# RF_Front_End.net
KiCad netlist of a schematic drawn in Altium Designer
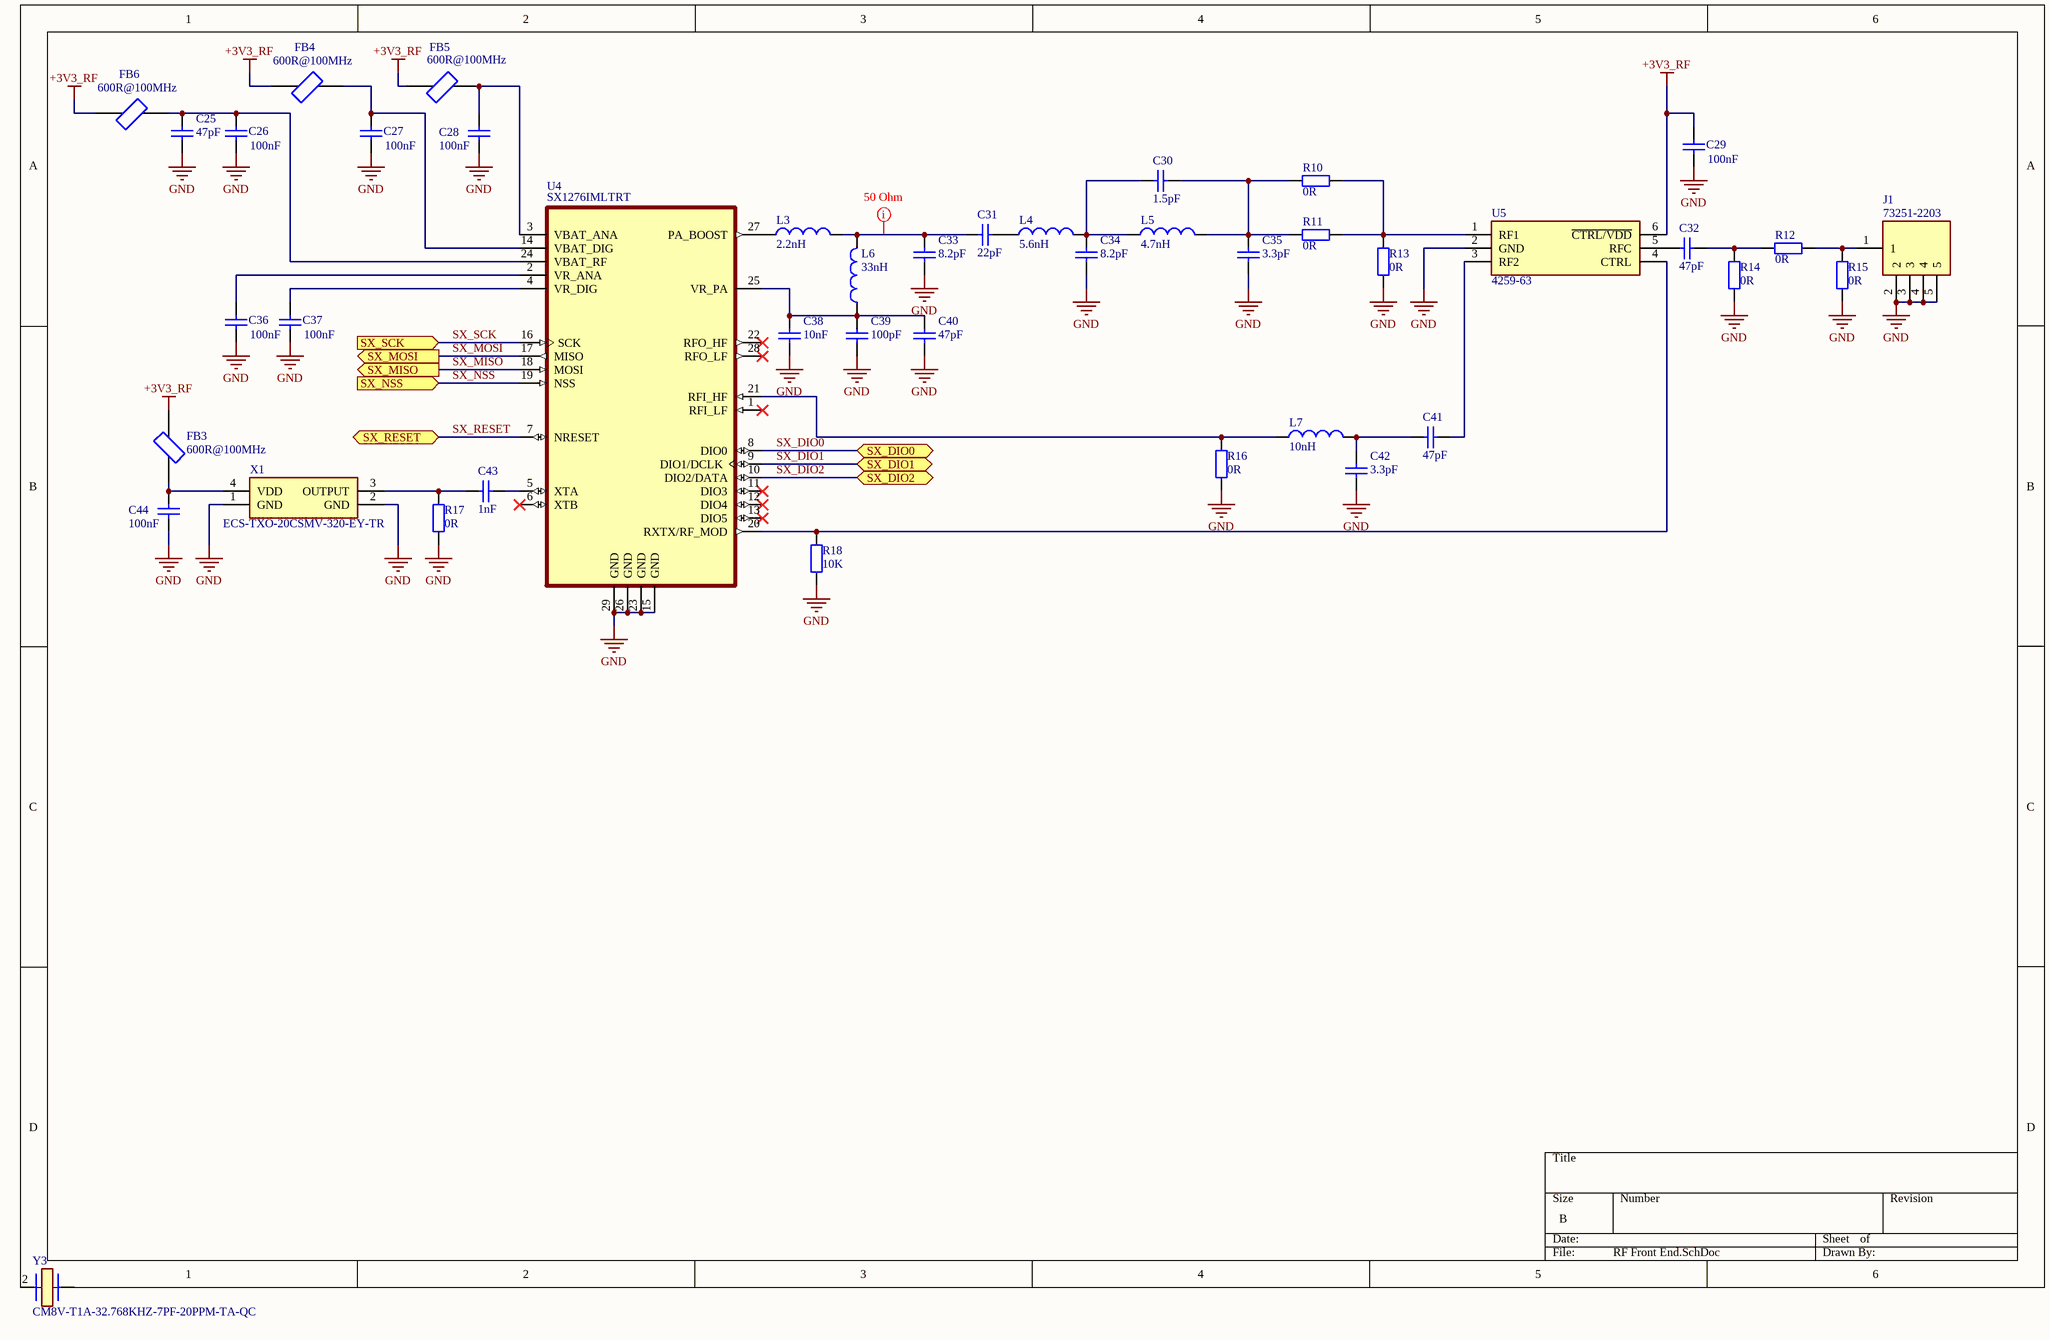
[diagram p0: RF Front End.SchDoc]

(export (version "E")
  (design (tool "Eeschema 10.0.6"))
  (components
    (comp (ref "C25")
      (value "47pF")
      (footprint "0402")
      (description "Capacitor")
      (fields (field (name "Comment") "Cap") (field (name "PUBLISHER") "Altium Limited"))
      (libsource (lib "Miscellaneous Devices") (part "Cap"))
    )
    (comp (ref "C26")
      (value "100nF")
      (footprint "0402")
      (description "Capacitor")
      (fields (field (name "PUBLISHER") "Altium Limited"))
      (libsource (lib "Miscellaneous Devices") (part "Cap"))
    )
    (comp (ref "C27")
      (value "100nF")
      (footprint "0402")
      (description "Capacitor")
      (fields (field (name "PUBLISHER") "Altium Limited"))
      (libsource (lib "Miscellaneous Devices") (part "Cap"))
    )
    (comp (ref "C28")
      (value "100nF")
      (footprint "0402")
      (description "Capacitor")
      (fields (field (name "PUBLISHER") "Altium Limited"))
      (libsource (lib "Miscellaneous Devices") (part "Cap"))
    )
    (comp (ref "C29")
      (value "100nF")
      (footprint "0402")
      (description "Capacitor")
      (fields (field (name "PUBLISHER") "Altium Limited"))
      (libsource (lib "Miscellaneous Devices") (part "Cap"))
    )
    (comp (ref "C30")
      (value "1.5pF")
      (footprint "0402")
      (description "Capacitor")
      (fields (field (name "Comment") "Cap") (field (name "PUBLISHER") "Altium Limited"))
      (libsource (lib "Miscellaneous Devices") (part "Cap"))
    )
    (comp (ref "C31")
      (value "22pF")
      (footprint "0402")
      (description "Capacitor")
      (fields (field (name "Comment") "Cap") (field (name "PUBLISHER") "Altium Limited"))
      (libsource (lib "Miscellaneous Devices") (part "Cap"))
    )
    (comp (ref "C32")
      (value "47pF")
      (footprint "0402")
      (description "Capacitor")
      (fields (field (name "Comment") "Cap") (field (name "PUBLISHER") "Altium Limited"))
      (libsource (lib "Miscellaneous Devices") (part "Cap"))
    )
    (comp (ref "C33")
      (value "8.2pF")
      (footprint "0402")
      (description "Capacitor")
      (fields (field (name "Comment") "Cap") (field (name "PUBLISHER") "Altium Limited"))
      (libsource (lib "Miscellaneous Devices") (part "Cap"))
    )
    (comp (ref "C34")
      (value "8.2pF")
      (footprint "0402")
      (description "Capacitor")
      (fields (field (name "Comment") "Cap") (field (name "PUBLISHER") "Altium Limited"))
      (libsource (lib "Miscellaneous Devices") (part "Cap"))
    )
    (comp (ref "C35")
      (value "3.3pF")
      (footprint "0402")
      (description "Capacitor")
      (fields (field (name "Comment") "Cap") (field (name "PUBLISHER") "Altium Limited"))
      (libsource (lib "Miscellaneous Devices") (part "Cap"))
    )
    (comp (ref "C36")
      (value "100nF")
      (footprint "0402")
      (description "Capacitor")
      (fields (field (name "PUBLISHER") "Altium Limited"))
      (libsource (lib "Miscellaneous Devices") (part "Cap"))
    )
    (comp (ref "C37")
      (value "100nF")
      (footprint "0402")
      (description "Capacitor")
      (fields (field (name "PUBLISHER") "Altium Limited"))
      (libsource (lib "Miscellaneous Devices") (part "Cap"))
    )
    (comp (ref "C38")
      (value "10nF")
      (footprint "0402")
      (description "Capacitor")
      (fields (field (name "Comment") "Cap") (field (name "PUBLISHER") "Altium Limited"))
      (libsource (lib "Miscellaneous Devices") (part "Cap"))
    )
    (comp (ref "C39")
      (value "100pF")
      (footprint "0402")
      (description "Capacitor")
      (fields (field (name "Comment") "Cap") (field (name "PUBLISHER") "Altium Limited"))
      (libsource (lib "Miscellaneous Devices") (part "Cap"))
    )
    (comp (ref "C40")
      (value "47pF")
      (footprint "0402")
      (description "Capacitor")
      (fields (field (name "Comment") "Cap") (field (name "PUBLISHER") "Altium Limited"))
      (libsource (lib "Miscellaneous Devices") (part "Cap"))
    )
    (comp (ref "C41")
      (value "47pF")
      (footprint "0402")
      (description "Capacitor")
      (fields (field (name "Comment") "Cap") (field (name "PUBLISHER") "Altium Limited"))
      (libsource (lib "Miscellaneous Devices") (part "Cap"))
    )
    (comp (ref "C42")
      (value "3.3pF")
      (footprint "0402")
      (description "Capacitor")
      (fields (field (name "Comment") "Cap") (field (name "PUBLISHER") "Altium Limited"))
      (libsource (lib "Miscellaneous Devices") (part "Cap"))
    )
    (comp (ref "C43")
      (value "1nF")
      (footprint "0402")
      (description "Capacitor")
      (fields (field (name "PUBLISHER") "Altium Limited"))
      (libsource (lib "Miscellaneous Devices") (part "Cap"))
    )
    (comp (ref "C44")
      (value "100nF")
      (footprint "0402")
      (description "Capacitor")
      (fields (field (name "PUBLISHER") "Altium Limited"))
      (libsource (lib "Miscellaneous Devices") (part "Cap"))
    )
    (comp (ref "FB3")
      (value "600R@100MHz")
      (footprint "0402 Ferrite Bead")
      (description "Ferrite Beads FERRITE BEAD 600 OHM 0603 1LN")
      (fields (field (name "MF") "Laird-Signal Integrity Products") (field (name "MP") "MI0805K400R-10"))
      (libsource (lib "Schematic_library") (part "Ferrite"))
    )
    (comp (ref "FB4")
      (value "600R@100MHz")
      (footprint "0402 Ferrite Bead")
      (description "Ferrite Beads FERRITE BEAD 600 OHM 0603 1LN")
      (fields (field (name "MF") "Laird-Signal Integrity Products") (field (name "MP") "MI0805K400R-10"))
      (libsource (lib "Schematic_library") (part "Ferrite"))
    )
    (comp (ref "FB5")
      (value "600R@100MHz")
      (footprint "0402 Ferrite Bead")
      (description "Ferrite Beads FERRITE BEAD 600 OHM 0603 1LN")
      (fields (field (name "MF") "Laird-Signal Integrity Products") (field (name "MP") "MI0805K400R-10"))
      (libsource (lib "Schematic_library") (part "Ferrite"))
    )
    (comp (ref "FB6")
      (value "600R@100MHz")
      (footprint "0402 Ferrite Bead")
      (description "Ferrite Beads FERRITE BEAD 600 OHM 0603 1LN")
      (fields (field (name "MF") "Laird-Signal Integrity Products") (field (name "MP") "MI0805K400R-10"))
      (libsource (lib "Schematic_library") (part "Ferrite"))
    )
    (comp (ref "J1")
      (value "73251-2203")
      (footprint "732512203")
      (description "RF Connectors / Coaxial Connectors Conn 50 Ohms, SMA Jack, Right-Angle PCB, Gold")
      (fields (field (name "MOUSER PART NUMBER") "538-73251-2203"))
      (libsource (lib "Schematic_library") (part "73251-2203"))
    )
    (comp (ref "L3")
      (value "2.2nH")
      (footprint "0402-A")
      (description "Inductor")
      (fields (field (name "PUBLISHER") "Altium Limited"))
      (libsource (lib "Miscellaneous Devices") (part "Inductor"))
    )
    (comp (ref "L4")
      (value "5.6nH")
      (footprint "0402-A")
      (description "Inductor")
      (fields (field (name "PUBLISHER") "Altium Limited"))
      (libsource (lib "Miscellaneous Devices") (part "Inductor"))
    )
    (comp (ref "L5")
      (value "4.7nH")
      (footprint "0402-A")
      (description "Inductor")
      (fields (field (name "PUBLISHER") "Altium Limited"))
      (libsource (lib "Miscellaneous Devices") (part "Inductor"))
    )
    (comp (ref "L6")
      (value "33nH")
      (footprint "0402-A")
      (description "Inductor")
      (fields (field (name "PUBLISHER") "Altium Limited"))
      (libsource (lib "Miscellaneous Devices") (part "Inductor"))
    )
    (comp (ref "L7")
      (value "10nH")
      (footprint "0402-A")
      (description "Inductor")
      (fields (field (name "PUBLISHER") "Altium Limited"))
      (libsource (lib "Miscellaneous Devices") (part "Inductor"))
    )
    (comp (ref "R10")
      (value "0R")
      (footprint "SMD-0402-RES")
      (description "Resistor")
      (fields (field (name "PUBLISHER") "Altium Limited"))
      (libsource (lib "") (part "Res2_2"))
    )
    (comp (ref "R11")
      (value "0R")
      (footprint "SMD-0402-RES")
      (description "Resistor")
      (fields (field (name "PUBLISHER") "Altium Limited"))
      (libsource (lib "") (part "Res2_2"))
    )
    (comp (ref "R12")
      (value "0R")
      (footprint "SMD-0402-RES")
      (description "Resistor")
      (fields (field (name "PUBLISHER") "Altium Limited"))
      (libsource (lib "") (part "Res2_1"))
    )
    (comp (ref "R13")
      (value "0R")
      (footprint "SMD-0402-RES")
      (description "Resistor")
      (fields (field (name "PUBLISHER") "Altium Limited"))
      (libsource (lib "Miscellaneous Devices") (part "Res2"))
    )
    (comp (ref "R14")
      (value "0R")
      (footprint "SMD-0402-RES")
      (description "Resistor")
      (fields (field (name "PUBLISHER") "Altium Limited"))
      (libsource (lib "Miscellaneous Devices") (part "Res2"))
    )
    (comp (ref "R15")
      (value "0R")
      (footprint "SMD-0402-RES")
      (description "Resistor")
      (fields (field (name "PUBLISHER") "Altium Limited"))
      (libsource (lib "Miscellaneous Devices") (part "Res2"))
    )
    (comp (ref "R16")
      (value "0R")
      (footprint "SMD-0402-RES")
      (description "Resistor")
      (fields (field (name "PUBLISHER") "Altium Limited"))
      (libsource (lib "Miscellaneous Devices") (part "Res2"))
    )
    (comp (ref "R17")
      (value "0R")
      (footprint "SMD-0402-RES")
      (description "Resistor")
      (fields (field (name "PUBLISHER") "Altium Limited"))
      (libsource (lib "Miscellaneous Devices") (part "Res2"))
    )
    (comp (ref "R18")
      (value "10K")
      (footprint "SMD-0402-RES")
      (description "Resistor")
      (fields (field (name "PUBLISHER") "Altium Limited"))
      (libsource (lib "Miscellaneous Devices") (part "Res2"))
    )
    (comp (ref "U4")
      (value "SX1276IMLTRT")
      (footprint "SX1276IMLTRT")
      (description "IC RF TxRx Only 802.15.4 LoRaâ„¢ 137MHz ~ 1.02GHz 28-VQFN Exposed Pad")
      (fields (field (name "MF") "Semtech Corporation"))
      (libsource (lib "Schematic_library") (part "SX1276IMLTRT"))
    )
    (comp (ref "U5")
      (value "4259-63")
      (footprint "4259-63")
      (description "RF switch IC")
      (fields (field (name "MOUSER PART NUMBER") "81-4259-63"))
      (libsource (lib "Schematic_library") (part "4259-63"))
    )
    (comp (ref "X1")
      (value "ECS-TXO-20CSMV-320-EY-TR")
      (footprint "ECS-TXO-20CSMV-320-EY-TR")
      (description "TCXO Oscillators MultiVolt TCXO,32MHz,+/-2.5ppm,1.7V 3.465V,2.5 mA,-30 C 85 C, 2.00mm x 1.60mm")
      (fields (field (name "MOUSER PART NUMBER") "520-TXO20CSMV320EYTR"))
      (libsource (lib "Schematic_library") (part "ECS-TXO-20CSMV-320-EY-TR"))
    )
    (comp (ref "Y3")
      (value "CM8V-T1A-32.768KHZ-7PF-20PPM-TA-QC")
      (footprint "SamacSys:CM8V32768TA020125")
      (description "Crystal or Oscillator")
      (fields (field (name "MOUSER PART NUMBER") "428-201436-MC01"))
      (libsource (lib "*") (part "CM8V-T1A-32.768KHZ-7PF-20PPM-TA-QC"))
    )
  )
  (nets
    (net (code "1") (name "+3V3_RF") (class "Default")
      (node (ref "C29") (pin "2") (pinfunction "2_2") (pintype "passive"))
      (node (ref "FB3") (pin "2") (pinfunction "2_2") (pintype "passive"))
      (node (ref "FB4") (pin "1") (pinfunction "1_1") (pintype "passive"))
      (node (ref "FB5") (pin "1") (pinfunction "1_1") (pintype "passive"))
      (node (ref "FB6") (pin "1") (pinfunction "1_1") (pintype "passive"))
      (node (ref "U5") (pin "6") (pinfunction "~{CTRL/VDD}_6") (pintype "passive"))
    )
    (net (code "2") (name "/SX_DIO0") (class "Default")
      (node (ref "U4") (pin "8") (pinfunction "DIO0_8") (pintype "bidirectional"))
    )
    (net (code "3") (name "/SX_DIO1") (class "Default")
      (node (ref "U4") (pin "9") (pinfunction "DIO1/DCLK_9") (pintype "bidirectional"))
    )
    (net (code "4") (name "/SX_DIO2") (class "Default")
      (node (ref "U4") (pin "10") (pinfunction "DIO2/DATA_10") (pintype "bidirectional"))
    )
    (net (code "5") (name "/SX_MISO") (class "Default")
      (node (ref "U4") (pin "18") (pinfunction "MOSI_18") (pintype "input"))
    )
    (net (code "6") (name "/SX_MOSI") (class "Default")
      (node (ref "U4") (pin "17") (pinfunction "MISO_17") (pintype "output"))
    )
    (net (code "7") (name "/SX_NSS") (class "Default")
      (node (ref "U4") (pin "19") (pinfunction "NSS_19") (pintype "input"))
    )
    (net (code "8") (name "/SX_RESET") (class "Default")
      (node (ref "U4") (pin "7") (pinfunction "NRESET_7") (pintype "bidirectional"))
    )
    (net (code "9") (name "/SX_SCK") (class "Default")
      (node (ref "U4") (pin "16") (pinfunction "SCK_16") (pintype "input"))
    )
    (net (code "10") (name "GND") (class "Default")
      (node (ref "C25") (pin "1") (pinfunction "1_1") (pintype "passive"))
      (node (ref "C26") (pin "1") (pinfunction "1_1") (pintype "passive"))
      (node (ref "C27") (pin "1") (pinfunction "1_1") (pintype "passive"))
      (node (ref "C28") (pin "1") (pinfunction "1_1") (pintype "passive"))
      (node (ref "C29") (pin "1") (pinfunction "1_1") (pintype "passive"))
      (node (ref "C33") (pin "1") (pinfunction "1_1") (pintype "passive"))
      (node (ref "C34") (pin "1") (pinfunction "1_1") (pintype "passive"))
      (node (ref "C35") (pin "1") (pinfunction "1_1") (pintype "passive"))
      (node (ref "C36") (pin "1") (pinfunction "1_1") (pintype "passive"))
      (node (ref "C37") (pin "1") (pinfunction "1_1") (pintype "passive"))
      (node (ref "C38") (pin "1") (pinfunction "1_1") (pintype "passive"))
      (node (ref "C39") (pin "1") (pinfunction "1_1") (pintype "passive"))
      (node (ref "C40") (pin "1") (pinfunction "1_1") (pintype "passive"))
      (node (ref "C42") (pin "1") (pinfunction "1_1") (pintype "passive"))
      (node (ref "C44") (pin "1") (pinfunction "1_1") (pintype "passive"))
      (node (ref "J1") (pin "2") (pinfunction "2_2") (pintype "passive"))
      (node (ref "J1") (pin "3") (pinfunction "3_3") (pintype "passive"))
      (node (ref "J1") (pin "4") (pinfunction "4_4") (pintype "passive"))
      (node (ref "J1") (pin "5") (pinfunction "5_5") (pintype "passive"))
      (node (ref "R13") (pin "1") (pinfunction "1_1") (pintype "passive"))
      (node (ref "R14") (pin "1") (pinfunction "1_1") (pintype "passive"))
      (node (ref "R15") (pin "1") (pinfunction "1_1") (pintype "passive"))
      (node (ref "R16") (pin "1") (pinfunction "1_1") (pintype "passive"))
      (node (ref "R17") (pin "1") (pinfunction "1_1") (pintype "passive"))
      (node (ref "R18") (pin "1") (pinfunction "1_1") (pintype "passive"))
      (node (ref "U4") (pin "15") (pinfunction "GND_15") (pintype "power_in"))
      (node (ref "U4") (pin "23") (pinfunction "GND_23") (pintype "power_in"))
      (node (ref "U4") (pin "26") (pinfunction "GND_26") (pintype "power_in"))
      (node (ref "U4") (pin "29") (pinfunction "GND_29") (pintype "power_in"))
      (node (ref "U5") (pin "2") (pinfunction "GND_2") (pintype "passive"))
      (node (ref "X1") (pin "1") (pinfunction "GND_1") (pintype "passive"))
      (node (ref "X1") (pin "2") (pinfunction "GND_2") (pintype "passive"))
    )
    (net (code "11") (name "Net-(C30-Pad1)") (class "Default")
      (node (ref "C30") (pin "1") (pinfunction "1_1") (pintype "passive"))
      (node (ref "C35") (pin "2") (pinfunction "2_2") (pintype "passive"))
      (node (ref "L5") (pin "2") (pinfunction "2_2") (pintype "passive"))
      (node (ref "R10") (pin "1") (pinfunction "1_1") (pintype "passive"))
      (node (ref "R11") (pin "1") (pinfunction "1_1") (pintype "passive"))
    )
    (net (code "12") (name "Net-(C30-Pad2)") (class "Default")
      (node (ref "C30") (pin "2") (pinfunction "2_2") (pintype "passive"))
      (node (ref "C34") (pin "2") (pinfunction "2_2") (pintype "passive"))
      (node (ref "L4") (pin "2") (pinfunction "2_2") (pintype "passive"))
      (node (ref "L5") (pin "1") (pinfunction "1_1") (pintype "passive"))
    )
    (net (code "13") (name "Net-(C31-Pad1)") (class "Default")
      (node (ref "C31") (pin "1") (pinfunction "1_1") (pintype "passive"))
      (node (ref "L4") (pin "1") (pinfunction "1_1") (pintype "passive"))
    )
    (net (code "14") (name "Net-(C31-Pad2)") (class "Default")
      (node (ref "C31") (pin "2") (pinfunction "2_2") (pintype "passive"))
      (node (ref "C33") (pin "2") (pinfunction "2_2") (pintype "passive"))
      (node (ref "L3") (pin "2") (pinfunction "2_2") (pintype "passive"))
      (node (ref "L6") (pin "2") (pinfunction "2_2") (pintype "passive"))
    )
    (net (code "15") (name "Net-(C32-Pad1)") (class "Default")
      (node (ref "C32") (pin "1") (pinfunction "1_1") (pintype "passive"))
      (node (ref "R12") (pin "2") (pinfunction "2_2") (pintype "passive"))
      (node (ref "R14") (pin "2") (pinfunction "2_2") (pintype "passive"))
    )
    (net (code "16") (name "Net-(C41-Pad2)") (class "Default")
      (node (ref "C41") (pin "2") (pinfunction "2_2") (pintype "passive"))
      (node (ref "C42") (pin "2") (pinfunction "2_2") (pintype "passive"))
      (node (ref "L7") (pin "2") (pinfunction "2_2") (pintype "passive"))
    )
    (net (code "17") (name "Net-(J1-Pad1)") (class "Default")
      (node (ref "J1") (pin "1") (pinfunction "1_1") (pintype "passive"))
      (node (ref "R12") (pin "1") (pinfunction "1_1") (pintype "passive"))
      (node (ref "R15") (pin "2") (pinfunction "2_2") (pintype "passive"))
    )
    (net (code "18") (name "Net-(U4-PA_BOOST)") (class "Default")
      (node (ref "L3") (pin "1") (pinfunction "1_1") (pintype "passive"))
      (node (ref "U4") (pin "27") (pinfunction "PA_BOOST_27") (pintype "output"))
    )
    (net (code "19") (name "Net-(U4-RFI_HF)") (class "Default")
      (node (ref "L7") (pin "1") (pinfunction "1_1") (pintype "passive"))
      (node (ref "R16") (pin "2") (pinfunction "2_2") (pintype "passive"))
      (node (ref "U4") (pin "21") (pinfunction "RFI_HF_21") (pintype "input"))
    )
    (net (code "20") (name "Net-(U4-RXTX{slash}RF_MOD)") (class "Default")
      (node (ref "R18") (pin "2") (pinfunction "2_2") (pintype "passive"))
      (node (ref "U4") (pin "20") (pinfunction "RXTX/RF_MOD_20") (pintype "output"))
      (node (ref "U5") (pin "4") (pinfunction "CTRL_4") (pintype "passive"))
    )
    (net (code "21") (name "Net-(U4-VBAT_ANA)") (class "Default")
      (node (ref "C28") (pin "2") (pinfunction "2_2") (pintype "passive"))
      (node (ref "FB5") (pin "2") (pinfunction "2_2") (pintype "passive"))
      (node (ref "U4") (pin "3") (pinfunction "VBAT_ANA_3") (pintype "power_in"))
    )
    (net (code "22") (name "Net-(U4-VBAT_DIG)") (class "Default")
      (node (ref "C27") (pin "2") (pinfunction "2_2") (pintype "passive"))
      (node (ref "FB4") (pin "2") (pinfunction "2_2") (pintype "passive"))
      (node (ref "U4") (pin "14") (pinfunction "VBAT_DIG_14") (pintype "power_in"))
    )
    (net (code "23") (name "Net-(U4-VBAT_RF)") (class "Default")
      (node (ref "C25") (pin "2") (pinfunction "2_2") (pintype "passive"))
      (node (ref "C26") (pin "2") (pinfunction "2_2") (pintype "passive"))
      (node (ref "FB6") (pin "2") (pinfunction "2_2") (pintype "passive"))
      (node (ref "U4") (pin "24") (pinfunction "VBAT_RF_24") (pintype "power_in"))
    )
    (net (code "24") (name "Net-(U4-VR_ANA)") (class "Default")
      (node (ref "C36") (pin "2") (pinfunction "2_2") (pintype "passive"))
      (node (ref "U4") (pin "2") (pinfunction "VR_ANA_2") (pintype "power_in"))
    )
    (net (code "25") (name "Net-(U4-VR_DIG)") (class "Default")
      (node (ref "C37") (pin "2") (pinfunction "2_2") (pintype "passive"))
      (node (ref "U4") (pin "4") (pinfunction "VR_DIG_4") (pintype "power_in"))
    )
    (net (code "26") (name "Net-(U4-VR_PA)") (class "Default")
      (node (ref "C38") (pin "2") (pinfunction "2_2") (pintype "passive"))
      (node (ref "C39") (pin "2") (pinfunction "2_2") (pintype "passive"))
      (node (ref "C40") (pin "2") (pinfunction "2_2") (pintype "passive"))
      (node (ref "L6") (pin "1") (pinfunction "1_1") (pintype "passive"))
      (node (ref "U4") (pin "25") (pinfunction "VR_PA_25") (pintype "power_in"))
    )
    (net (code "27") (name "Net-(U4-XTA)") (class "Default")
      (node (ref "C43") (pin "1") (pinfunction "1_1") (pintype "passive"))
      (node (ref "U4") (pin "5") (pinfunction "XTA_5") (pintype "bidirectional"))
    )
    (net (code "28") (name "Net-(U5-RF1)") (class "Default")
      (node (ref "R10") (pin "2") (pinfunction "2_2") (pintype "passive"))
      (node (ref "R11") (pin "2") (pinfunction "2_2") (pintype "passive"))
      (node (ref "R13") (pin "2") (pinfunction "2_2") (pintype "passive"))
      (node (ref "U5") (pin "1") (pinfunction "RF1_1") (pintype "passive"))
    )
    (net (code "29") (name "Net-(U5-RF2)") (class "Default")
      (node (ref "C41") (pin "1") (pinfunction "1_1") (pintype "passive"))
      (node (ref "U5") (pin "3") (pinfunction "RF2_3") (pintype "passive"))
    )
    (net (code "30") (name "Net-(U5-RFC)") (class "Default")
      (node (ref "C32") (pin "2") (pinfunction "2_2") (pintype "passive"))
      (node (ref "U5") (pin "5") (pinfunction "RFC_5") (pintype "passive"))
    )
    (net (code "31") (name "Net-(X1-OUTPUT)") (class "Default")
      (node (ref "C43") (pin "2") (pinfunction "2_2") (pintype "passive"))
      (node (ref "R17") (pin "2") (pinfunction "2_2") (pintype "passive"))
      (node (ref "X1") (pin "3") (pinfunction "OUTPUT_3") (pintype "passive"))
    )
    (net (code "32") (name "Net-(X1-VDD)") (class "Default")
      (node (ref "C44") (pin "2") (pinfunction "2_2") (pintype "passive"))
      (node (ref "FB3") (pin "1") (pinfunction "1_1") (pintype "passive"))
      (node (ref "X1") (pin "4") (pinfunction "VDD_4") (pintype "passive"))
    )
    (net (code "33") (name "unconnected-(U4-DIO3-Pad11)") (class "Default")
      (node (ref "U4") (pin "11") (pinfunction "DIO3_11") (pintype "bidirectional+no_connect"))
    )
    (net (code "34") (name "unconnected-(U4-DIO4-Pad12)") (class "Default")
      (node (ref "U4") (pin "12") (pinfunction "DIO4_12") (pintype "bidirectional+no_connect"))
    )
    (net (code "35") (name "unconnected-(U4-DIO5-Pad13)") (class "Default")
      (node (ref "U4") (pin "13") (pinfunction "DIO5_13") (pintype "bidirectional+no_connect"))
    )
    (net (code "36") (name "unconnected-(U4-RFI_LF-Pad1)") (class "Default")
      (node (ref "U4") (pin "1") (pinfunction "RFI_LF_1") (pintype "input+no_connect"))
    )
    (net (code "37") (name "unconnected-(U4-RFO_HF-Pad22)") (class "Default")
      (node (ref "U4") (pin "22") (pinfunction "RFO_HF_22") (pintype "output+no_connect"))
    )
    (net (code "38") (name "unconnected-(U4-RFO_LF-Pad28)") (class "Default")
      (node (ref "U4") (pin "28") (pinfunction "RFO_LF_28") (pintype "output+no_connect"))
    )
    (net (code "39") (name "unconnected-(U4-XTB-Pad6)") (class "Default")
      (node (ref "U4") (pin "6") (pinfunction "XTB_6") (pintype "bidirectional+no_connect"))
    )
    (net (code "40") (name "unconnected-(Y3-Pad)") (class "Default")
      (node (ref "Y3") (pin "") (pintype "passive"))
    )
    (net (code "41") (name "unconnected-(Y3-X2-Pad2)") (class "Default")
      (node (ref "Y3") (pin "2") (pinfunction "X2_2") (pintype "passive"))
    )
  )
)
